# card.net
KiCad netlist of a schematic drawn in EAGLE
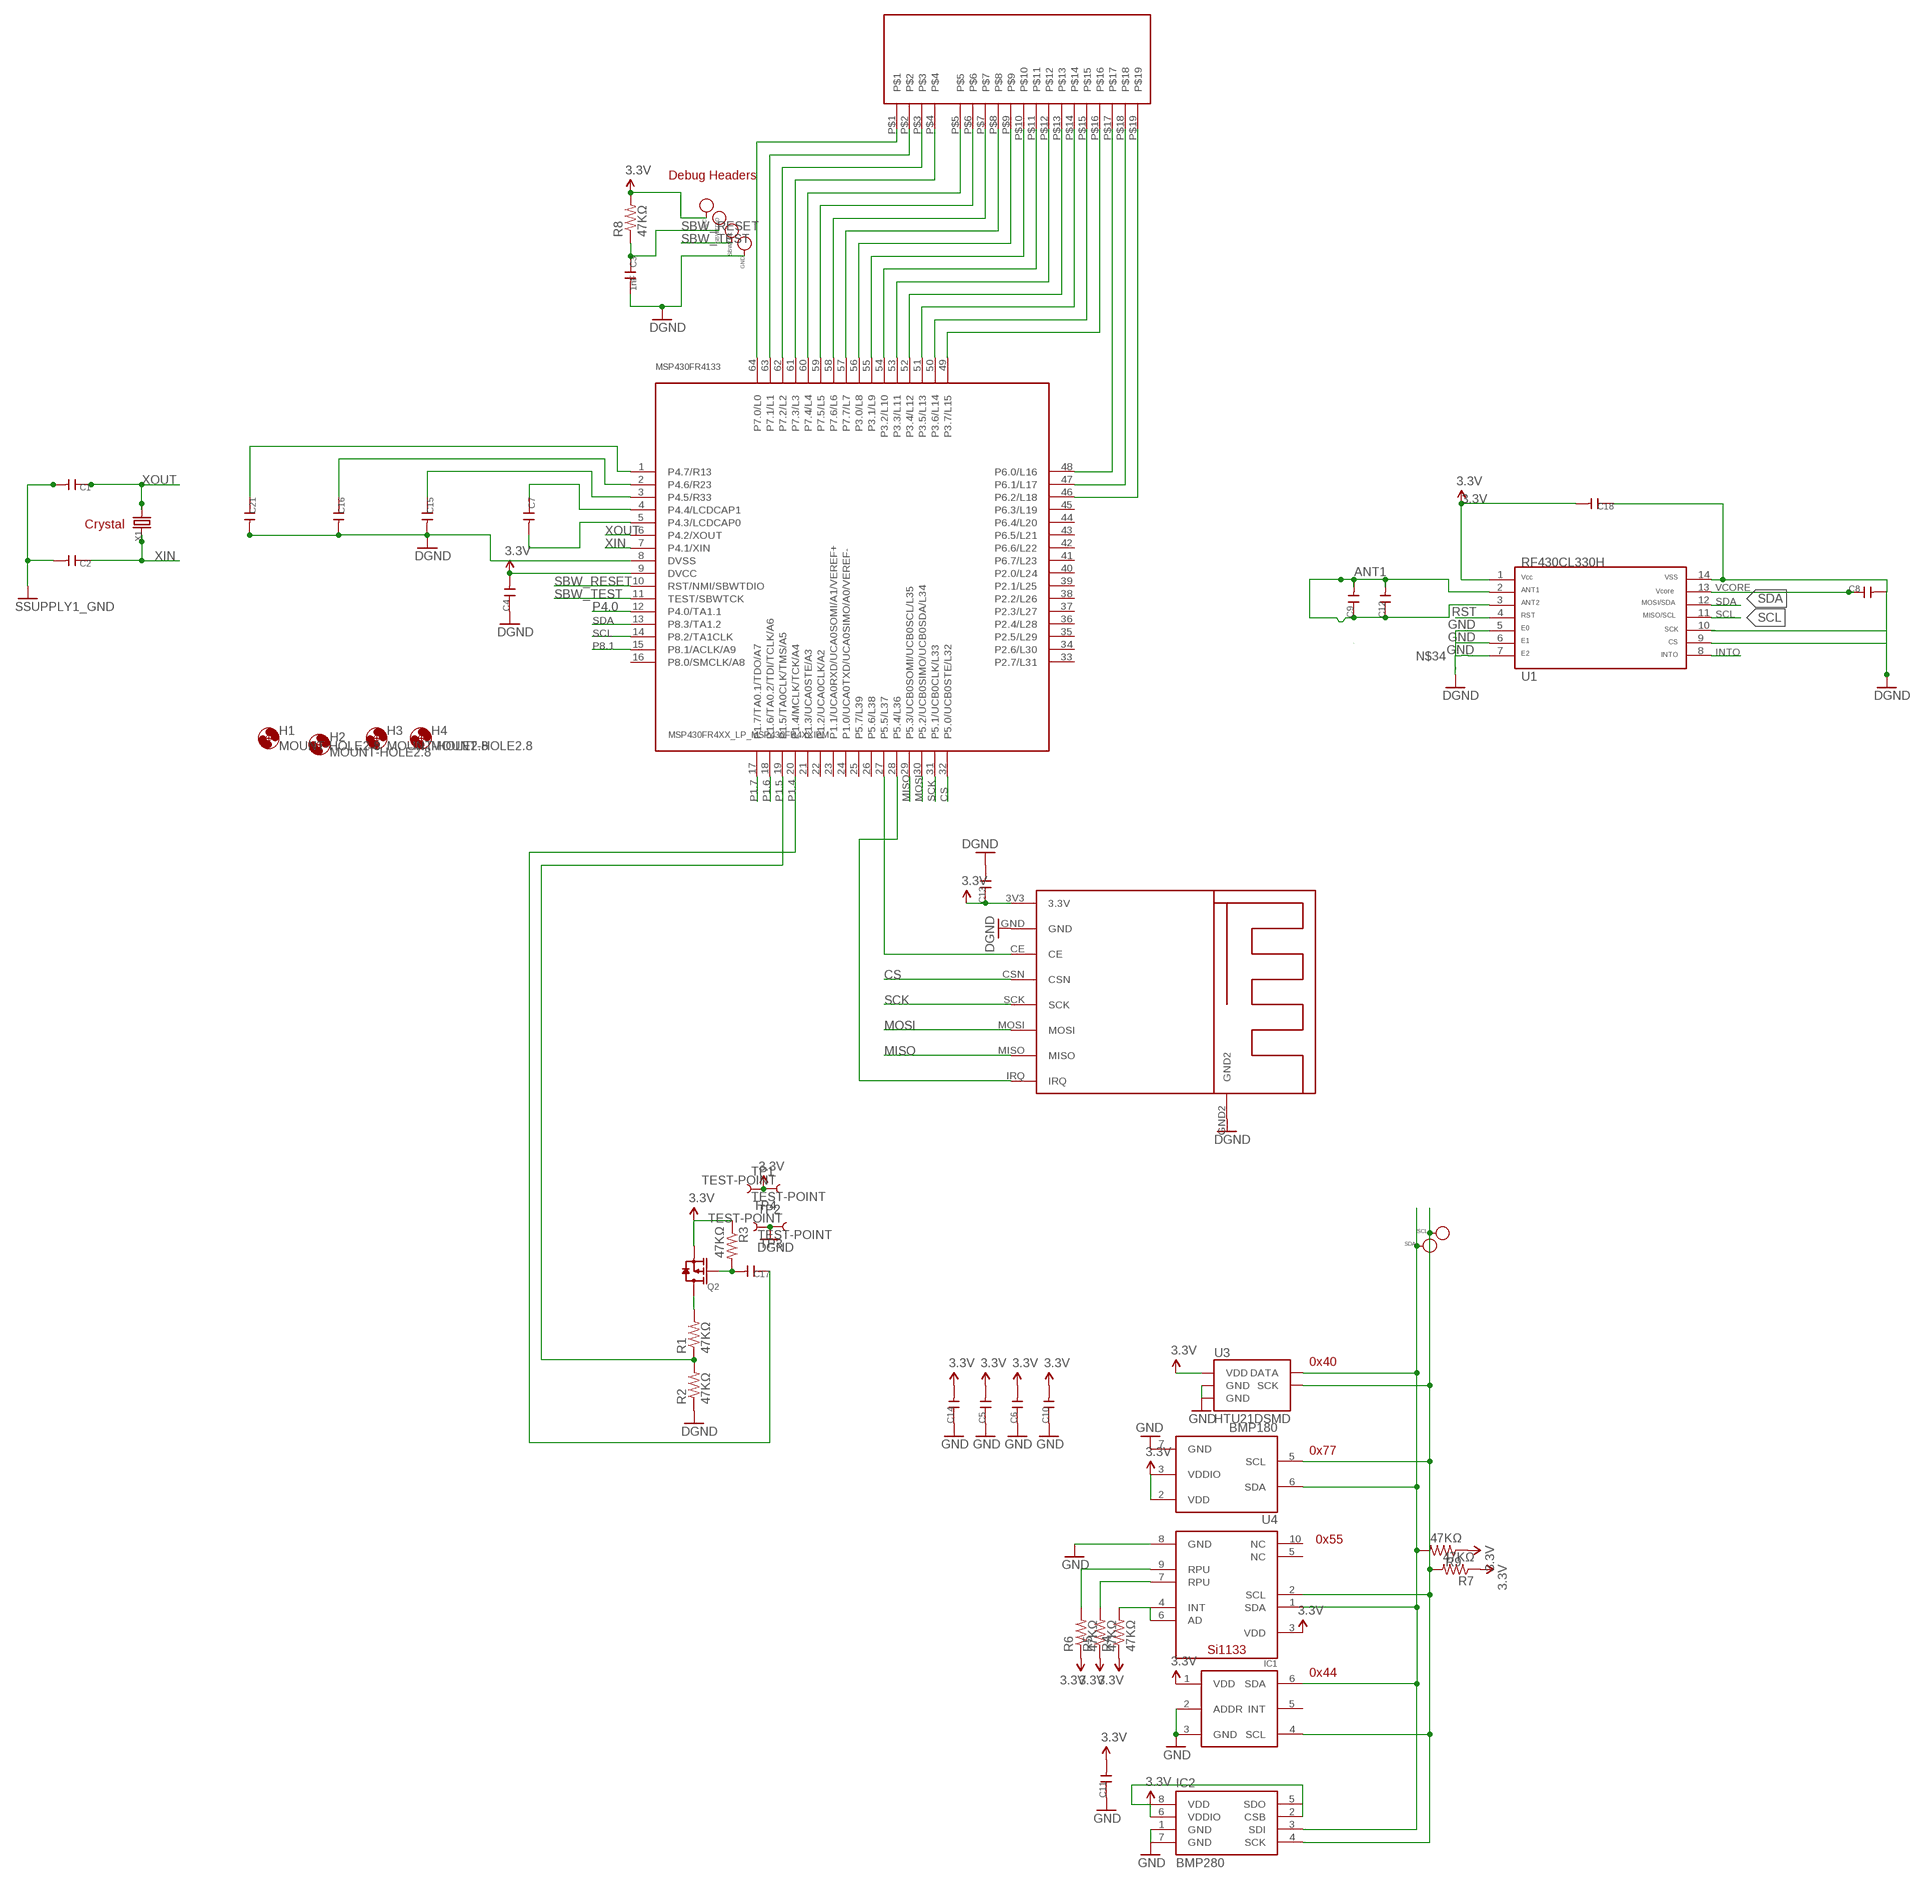
[diagram p0: schematic, sheet 1]

(export (version "E")
  (design (tool "Eeschema 10.0.6"))
  (components
    (comp (ref "C1")
      (value "C-0402")
      (footprint "eagle-import:C0402")
      (libsource (lib "eagle-import") (part "C-0402"))
    )
    (comp (ref "C2")
      (value "C-0402")
      (footprint "eagle-import:C0402")
      (libsource (lib "eagle-import") (part "C-0402"))
    )
    (comp (ref "C3")
      (value "1nF")
      (footprint "eagle-import:C0402")
      (libsource (lib "eagle-import") (part "C-0402"))
    )
    (comp (ref "C4")
      (value "C-0402")
      (footprint "eagle-import:C0402")
      (libsource (lib "eagle-import") (part "C-0402"))
    )
    (comp (ref "C5")
      (value "C-0402")
      (footprint "eagle-import:C0402")
      (libsource (lib "eagle-import") (part "C-0402"))
    )
    (comp (ref "C6")
      (value "C-0402")
      (footprint "eagle-import:C0402")
      (libsource (lib "eagle-import") (part "C-0402"))
    )
    (comp (ref "C7")
      (value "C-0402")
      (footprint "eagle-import:C0402")
      (libsource (lib "eagle-import") (part "C-0402"))
    )
    (comp (ref "C8")
      (value "C-0402")
      (footprint "eagle-import:C0402")
      (libsource (lib "eagle-import") (part "C-0402"))
    )
    (comp (ref "C9")
      (value "C-0402")
      (footprint "eagle-import:C0402")
      (libsource (lib "eagle-import") (part "C-0402"))
    )
    (comp (ref "C10")
      (value "C-0402")
      (footprint "eagle-import:C0402")
      (libsource (lib "eagle-import") (part "C-0402"))
    )
    (comp (ref "C11")
      (value "C-0402")
      (footprint "eagle-import:C0402")
      (libsource (lib "eagle-import") (part "C-0402"))
    )
    (comp (ref "C12")
      (value "C-0402")
      (footprint "eagle-import:C0402")
      (libsource (lib "eagle-import") (part "C-0402"))
    )
    (comp (ref "C13")
      (value "C-0603")
      (footprint "eagle-import:C0603")
      (libsource (lib "eagle-import") (part "C-0603"))
    )
    (comp (ref "C14")
      (value "C-0402")
      (footprint "eagle-import:C0402")
      (libsource (lib "eagle-import") (part "C-0402"))
    )
    (comp (ref "C15")
      (value "C-0402")
      (footprint "eagle-import:C0402")
      (libsource (lib "eagle-import") (part "C-0402"))
    )
    (comp (ref "C16")
      (value "C-0402")
      (footprint "eagle-import:C0402")
      (libsource (lib "eagle-import") (part "C-0402"))
    )
    (comp (ref "C17")
      (value "C-0402")
      (footprint "eagle-import:C0402")
      (libsource (lib "eagle-import") (part "C-0402"))
    )
    (comp (ref "C18")
      (value "C-0402")
      (footprint "eagle-import:C0402")
      (libsource (lib "eagle-import") (part "C-0402"))
    )
    (comp (ref "C21")
      (value "C-0402")
      (footprint "eagle-import:C0402")
      (libsource (lib "eagle-import") (part "C-0402"))
    )
    (comp (ref "GND")
      (value "PAD-TEST-POINT'4545'")
      (footprint "eagle-import:TP_4545")
      (fields (field (name "PARTNO") "DNP"))
      (libsource (lib "eagle-import") (part "PAD-TEST-POINT'4545'"))
    )
    (comp (ref "H1")
      (value "MOUNT-HOLE2.8")
      (footprint "eagle-import:2,8")
      (libsource (lib "eagle-import") (part "MOUNT-HOLE2.8"))
    )
    (comp (ref "H2")
      (value "MOUNT-HOLE2.8")
      (footprint "eagle-import:2,8")
      (libsource (lib "eagle-import") (part "MOUNT-HOLE2.8"))
    )
    (comp (ref "H3")
      (value "MOUNT-HOLE2.8")
      (footprint "eagle-import:2,8")
      (libsource (lib "eagle-import") (part "MOUNT-HOLE2.8"))
    )
    (comp (ref "H4")
      (value "MOUNT-HOLE2.8")
      (footprint "eagle-import:2,8")
      (libsource (lib "eagle-import") (part "MOUNT-HOLE2.8"))
    )
    (comp (ref "IC1")
      (value "SILICONLABS-SI1133")
      (footprint "eagle-import:SILICONLABS-SI1133")
      (libsource (lib "eagle-import") (part "SILICONLABS-SI1133"))
    )
    (comp (ref "IC2")
      (value "BMP280")
      (footprint "eagle-import:LGA")
      (libsource (lib "eagle-import") (part "BMP280"))
    )
    (comp (ref "MSP430FR4133")
      (value "MSP430FR4XX_LP_MSP430FR4XXIPM")
      (footprint "eagle-import:MSP430G6_LP_LQFP64")
      (libsource (lib "eagle-import") (part "MSP430FR4XX_LP_MSP430FR4XXIPM"))
    )
    (comp (ref "Q2")
      (value "MOSFET-P'SI2323CDS/SI2305DS<BR>'")
      (footprint "eagle-import:SOT23")
      (libsource (lib "eagle-import") (part "MOSFET-P'SI2323CDS/SI2305DS{lt}BR{gt}'"))
    )
    (comp (ref "R1")
      (value "47KΩ")
      (footprint "eagle-import:RCL_R1005")
      (libsource (lib "eagle-import") (part "RESISTOR_1005"))
    )
    (comp (ref "R2")
      (value "47KΩ")
      (footprint "eagle-import:RCL_R1005")
      (libsource (lib "eagle-import") (part "RESISTOR_1005"))
    )
    (comp (ref "R3")
      (value "47KΩ")
      (footprint "eagle-import:RCL_R1005")
      (libsource (lib "eagle-import") (part "RESISTOR_1005"))
    )
    (comp (ref "R4")
      (value "47KΩ")
      (footprint "eagle-import:RCL_R1005")
      (libsource (lib "eagle-import") (part "RESISTOR_1005"))
    )
    (comp (ref "R5")
      (value "47KΩ")
      (footprint "eagle-import:RCL_R1005")
      (libsource (lib "eagle-import") (part "RESISTOR_1005"))
    )
    (comp (ref "R6")
      (value "47KΩ")
      (footprint "eagle-import:RCL_R1005")
      (libsource (lib "eagle-import") (part "RESISTOR_1005"))
    )
    (comp (ref "R7")
      (value "47KΩ")
      (footprint "eagle-import:RCL_R1005")
      (libsource (lib "eagle-import") (part "RESISTOR_1005"))
    )
    (comp (ref "R8")
      (value "47KΩ")
      (footprint "eagle-import:RCL_R1005")
      (libsource (lib "eagle-import") (part "RESISTOR_1005"))
    )
    (comp (ref "R9")
      (value "47KΩ")
      (footprint "eagle-import:RCL_R1005")
      (libsource (lib "eagle-import") (part "RESISTOR_1005"))
    )
    (comp (ref "SBWTCK")
      (value "PAD-TEST-POINT'4545'")
      (footprint "eagle-import:TP_4545")
      (fields (field (name "PARTNO") "DNP"))
      (libsource (lib "eagle-import") (part "PAD-TEST-POINT'4545'"))
    )
    (comp (ref "SBWTDIO")
      (value "PAD-TEST-POINT'4545'")
      (footprint "eagle-import:TP_4545")
      (fields (field (name "PARTNO") "DNP"))
      (libsource (lib "eagle-import") (part "PAD-TEST-POINT'4545'"))
    )
    (comp (ref "SCL")
      (value "PAD-TEST-POINT'4545'")
      (footprint "eagle-import:TP_4545")
      (fields (field (name "PARTNO") "DNP"))
      (libsource (lib "eagle-import") (part "PAD-TEST-POINT'4545'"))
    )
    (comp (ref "SDA")
      (value "PAD-TEST-POINT'4545'")
      (footprint "eagle-import:TP_4545")
      (fields (field (name "PARTNO") "DNP"))
      (libsource (lib "eagle-import") (part "PAD-TEST-POINT'4545'"))
    )
    (comp (ref "TP1")
      (value "TEST-POINT")
      (footprint "eagle-import:BATTERY")
      (libsource (lib "eagle-import") (part "TEST-POINT"))
    )
    (comp (ref "TP2")
      (value "TEST-POINT")
      (footprint "eagle-import:BATTERY")
      (libsource (lib "eagle-import") (part "TEST-POINT"))
    )
    (comp (ref "TP3")
      (value "TEST-POINT")
      (footprint "eagle-import:BATTERY")
      (libsource (lib "eagle-import") (part "TEST-POINT"))
    )
    (comp (ref "TP4")
      (value "TEST-POINT")
      (footprint "eagle-import:BATTERY")
      (libsource (lib "eagle-import") (part "TEST-POINT"))
    )
    (comp (ref "U$1")
      (value "HUMIDITYTEMP_DISPLAY")
      (footprint "eagle-import:HUMIDITYTEMP_DISPLAY")
      (libsource (lib "eagle-import") (part "HUMIDITYTEMP_DISPLAY"))
    )
    (comp (ref "U$2")
      (value "NRF24MINI")
      (footprint "eagle-import:NRF24MINI")
      (libsource (lib "eagle-import") (part "NRF24MINI"))
    )
    (comp (ref "U$5")
      (value "TI-OPT3001")
      (footprint "eagle-import:TI-OPT3001")
      (libsource (lib "eagle-import") (part "TI-OPT3001"))
    )
    (comp (ref "U1")
      (value "RF430CL330H")
      (footprint "eagle-import:PW14")
      (libsource (lib "eagle-import") (part "RF430CL330H"))
    )
    (comp (ref "U3")
      (value "HTU21DSMD")
      (footprint "eagle-import:HTU21D")
      (libsource (lib "eagle-import") (part "HTU21DSMD"))
    )
    (comp (ref "U4")
      (value "BMP180")
      (footprint "eagle-import:BMP180")
      (libsource (lib "eagle-import") (part "BMP180"))
    )
    (comp (ref "VCC")
      (value "PAD-TEST-POINT'4545'")
      (footprint "eagle-import:TP_4545")
      (fields (field (name "PARTNO") "DNP"))
      (libsource (lib "eagle-import") (part "PAD-TEST-POINT'4545'"))
    )
    (comp (ref "X1")
      (value "CRYSTAL-3215")
      (footprint "eagle-import:2P-SMD-3.2X1.5")
      (libsource (lib "eagle-import") (part "CRYSTAL-3215"))
    )
  )
  (nets
    (net (code "1") (name "/ANT1") (class "Default")
      (node (ref "C12") (pin "1") (pinfunction "1_1") (pintype "passive"))
      (node (ref "C12") (pin "2") (pinfunction "2_2") (pintype "passive"))
      (node (ref "C9") (pin "1") (pinfunction "1_1") (pintype "passive"))
      (node (ref "C9") (pin "2") (pinfunction "2_2") (pintype "passive"))
      (node (ref "U1") (pin "2") (pinfunction "2_2") (pintype "bidirectional"))
      (node (ref "U1") (pin "3") (pinfunction "3_3") (pintype "bidirectional"))
    )
    (net (code "2") (name "/CS") (class "Default")
      (node (ref "MSP430FR4133") (pin "32") (pinfunction "P5.0/UCB0STE/L32_32") (pintype "bidirectional"))
      (node (ref "U$2") (pin "CSN") (pinfunction "CSN_CSN") (pintype "bidirectional"))
    )
    (net (code "3") (name "/INTO") (class "Default")
      (node (ref "U1") (pin "8") (pinfunction "8_8") (pintype "bidirectional"))
    )
    (net (code "4") (name "/MISO") (class "Default")
      (node (ref "MSP430FR4133") (pin "29") (pinfunction "P5.3/UCB0SOMI/UCB0SCL/L35_29") (pintype "bidirectional"))
      (node (ref "U$2") (pin "MISO") (pinfunction "MISO_MISO") (pintype "bidirectional"))
    )
    (net (code "5") (name "/MOSI") (class "Default")
      (node (ref "MSP430FR4133") (pin "30") (pinfunction "P5.2/UCB0SIMO/UCB0SDA/L34_30") (pintype "bidirectional"))
      (node (ref "U$2") (pin "MOSI") (pinfunction "MOSI_MOSI") (pintype "bidirectional"))
    )
    (net (code "6") (name "/P1.4") (class "Default")
      (node (ref "MSP430FR4133") (pin "19") (pinfunction "P1.5/TA0CLK/TMS/A5_19") (pintype "bidirectional"))
      (node (ref "R1") (pin "1") (pinfunction "1_1") (pintype "passive"))
      (node (ref "R2") (pin "2") (pinfunction "2_2") (pintype "passive"))
    )
    (net (code "7") (name "/P1.5") (class "Default")
      (node (ref "C17") (pin "1") (pinfunction "1_1") (pintype "passive"))
      (node (ref "MSP430FR4133") (pin "20") (pinfunction "P1.4/MCLK/TCK/A4_20") (pintype "bidirectional"))
    )
    (net (code "8") (name "/P1.6") (class "Default")
      (node (ref "MSP430FR4133") (pin "18") (pinfunction "P1.6/TA0.2/TDI/TCLK/A6_18") (pintype "bidirectional"))
    )
    (net (code "9") (name "/P1.7") (class "Default")
      (node (ref "MSP430FR4133") (pin "17") (pinfunction "P1.7/TA0.1/TDO/A7_17") (pintype "bidirectional"))
    )
    (net (code "10") (name "/P4.0") (class "Default")
      (node (ref "MSP430FR4133") (pin "12") (pinfunction "P4.0/TA1.1_12") (pintype "bidirectional"))
    )
    (net (code "11") (name "/P8.1") (class "Default")
      (node (ref "MSP430FR4133") (pin "15") (pinfunction "P8.1/ACLK/A9_15") (pintype "bidirectional"))
    )
    (net (code "12") (name "/RST") (class "Default")
      (node (ref "U1") (pin "4") (pinfunction "4_4") (pintype "bidirectional"))
    )
    (net (code "13") (name "/SBW_RESET") (class "Default")
      (node (ref "C3") (pin "1") (pinfunction "1_1") (pintype "passive"))
      (node (ref "MSP430FR4133") (pin "10") (pinfunction "RST/NMI/SBWTDIO_10") (pintype "bidirectional"))
      (node (ref "R8") (pin "1") (pinfunction "1_1") (pintype "passive"))
      (node (ref "SBWTDIO") (pin "T") (pinfunction "T_T") (pintype "bidirectional"))
    )
    (net (code "14") (name "/SBW_TEST") (class "Default")
      (node (ref "MSP430FR4133") (pin "11") (pinfunction "TEST/SBWTCK_11") (pintype "bidirectional"))
      (node (ref "SBWTCK") (pin "T") (pinfunction "T_T") (pintype "bidirectional"))
    )
    (net (code "15") (name "/SCK") (class "Default")
      (node (ref "MSP430FR4133") (pin "31") (pinfunction "P5.1/UCB0CLK/L33_31") (pintype "bidirectional"))
      (node (ref "U$2") (pin "SCK") (pinfunction "SCK_SCK") (pintype "bidirectional"))
    )
    (net (code "16") (name "/VCORE") (class "Default")
      (node (ref "C8") (pin "1") (pinfunction "1_1") (pintype "passive"))
      (node (ref "U1") (pin "13") (pinfunction "13_13") (pintype "bidirectional"))
    )
    (net (code "17") (name "/XIN") (class "Default")
      (node (ref "C2") (pin "1") (pinfunction "1_1") (pintype "passive"))
      (node (ref "MSP430FR4133") (pin "7") (pinfunction "P4.1/XIN_7") (pintype "bidirectional"))
      (node (ref "X1") (pin "1") (pinfunction "1_1") (pintype "passive"))
    )
    (net (code "18") (name "/XOUT") (class "Default")
      (node (ref "C1") (pin "1") (pinfunction "1_1") (pintype "passive"))
      (node (ref "MSP430FR4133") (pin "6") (pinfunction "P4.2/XOUT_6") (pintype "bidirectional"))
      (node (ref "X1") (pin "2") (pinfunction "2_2") (pintype "passive"))
    )
    (net (code "19") (name "3.3V") (class "Default")
      (node (ref "C10") (pin "2") (pinfunction "2_2") (pintype "passive"))
      (node (ref "C11") (pin "2") (pinfunction "2_2") (pintype "passive"))
      (node (ref "C13") (pin "1") (pinfunction "1_1") (pintype "passive"))
      (node (ref "C14") (pin "2") (pinfunction "2_2") (pintype "passive"))
      (node (ref "C18") (pin "2") (pinfunction "2_2") (pintype "passive"))
      (node (ref "C4") (pin "2") (pinfunction "2_2") (pintype "passive"))
      (node (ref "C5") (pin "2") (pinfunction "2_2") (pintype "passive"))
      (node (ref "C6") (pin "2") (pinfunction "2_2") (pintype "passive"))
      (node (ref "IC1") (pin "3") (pinfunction "VDD_3") (pintype "bidirectional"))
      (node (ref "IC2") (pin "2") (pinfunction "CSB_2") (pintype "input"))
      (node (ref "IC2") (pin "5") (pinfunction "SDO_5") (pintype "bidirectional"))
      (node (ref "IC2") (pin "6") (pinfunction "VDDIO_6") (pintype "input"))
      (node (ref "IC2") (pin "8") (pinfunction "VDD_8") (pintype "power_in"))
      (node (ref "MSP430FR4133") (pin "9") (pinfunction "DVCC_9") (pintype "bidirectional"))
      (node (ref "Q2") (pin "2") (pinfunction "S_2") (pintype "passive"))
      (node (ref "R3") (pin "1") (pinfunction "1_1") (pintype "passive"))
      (node (ref "R4") (pin "1") (pinfunction "1_1") (pintype "passive"))
      (node (ref "R5") (pin "1") (pinfunction "1_1") (pintype "passive"))
      (node (ref "R6") (pin "1") (pinfunction "1_1") (pintype "passive"))
      (node (ref "R7") (pin "1") (pinfunction "1_1") (pintype "passive"))
      (node (ref "R8") (pin "2") (pinfunction "2_2") (pintype "passive"))
      (node (ref "R9") (pin "1") (pinfunction "1_1") (pintype "passive"))
      (node (ref "TP1") (pin "P$1") (pinfunction "1_P$1") (pintype "bidirectional"))
      (node (ref "TP4") (pin "P$1") (pinfunction "1_P$1") (pintype "bidirectional"))
      (node (ref "U$2") (pin "3V3") (pinfunction "3.3V_3V3") (pintype "bidirectional"))
      (node (ref "U$5") (pin "1") (pinfunction "VDD_1") (pintype "bidirectional"))
      (node (ref "U1") (pin "1") (pinfunction "1_1") (pintype "bidirectional"))
      (node (ref "U3") (pin "VDD") (pinfunction "VDD_VDD") (pintype "power_in"))
      (node (ref "U4") (pin "2") (pinfunction "VDD_2") (pintype "power_in"))
      (node (ref "U4") (pin "3") (pinfunction "VDDIO_3") (pintype "power_in"))
      (node (ref "VCC") (pin "T") (pinfunction "T_T") (pintype "bidirectional"))
    )
    (net (code "20") (name "DGND") (class "Default")
      (node (ref "C1") (pin "2") (pinfunction "2_2") (pintype "passive"))
      (node (ref "C10") (pin "1") (pinfunction "1_1") (pintype "passive"))
      (node (ref "C11") (pin "1") (pinfunction "1_1") (pintype "passive"))
      (node (ref "C13") (pin "2") (pinfunction "2_2") (pintype "passive"))
      (node (ref "C14") (pin "1") (pinfunction "1_1") (pintype "passive"))
      (node (ref "C15") (pin "2") (pinfunction "2_2") (pintype "passive"))
      (node (ref "C16") (pin "2") (pinfunction "2_2") (pintype "passive"))
      (node (ref "C18") (pin "1") (pinfunction "1_1") (pintype "passive"))
      (node (ref "C2") (pin "2") (pinfunction "2_2") (pintype "passive"))
      (node (ref "C21") (pin "2") (pinfunction "2_2") (pintype "passive"))
      (node (ref "C3") (pin "2") (pinfunction "2_2") (pintype "passive"))
      (node (ref "C4") (pin "1") (pinfunction "1_1") (pintype "passive"))
      (node (ref "C5") (pin "1") (pinfunction "1_1") (pintype "passive"))
      (node (ref "C6") (pin "1") (pinfunction "1_1") (pintype "passive"))
      (node (ref "C8") (pin "2") (pinfunction "2_2") (pintype "passive"))
      (node (ref "GND") (pin "T") (pinfunction "T_T") (pintype "bidirectional"))
      (node (ref "IC1") (pin "8") (pinfunction "GND_8") (pintype "bidirectional"))
      (node (ref "IC2") (pin "1") (pinfunction "GND_1") (pintype "power_in"))
      (node (ref "IC2") (pin "7") (pinfunction "GND_7") (pintype "power_in"))
      (node (ref "MSP430FR4133") (pin "8") (pinfunction "DVSS_8") (pintype "bidirectional"))
      (node (ref "R2") (pin "1") (pinfunction "1_1") (pintype "passive"))
      (node (ref "TP2") (pin "P$1") (pinfunction "1_P$1") (pintype "bidirectional"))
      (node (ref "TP3") (pin "P$1") (pinfunction "1_P$1") (pintype "bidirectional"))
      (node (ref "U$2") (pin "GND") (pinfunction "GND_GND") (pintype "bidirectional"))
      (node (ref "U$2") (pin "GND2") (pinfunction "GND2_GND2") (pintype "bidirectional"))
      (node (ref "U$5") (pin "2") (pinfunction "ADDR_2") (pintype "bidirectional"))
      (node (ref "U$5") (pin "3") (pinfunction "GND_3") (pintype "bidirectional"))
      (node (ref "U1") (pin "10") (pinfunction "10_10") (pintype "bidirectional"))
      (node (ref "U1") (pin "14") (pinfunction "14_14") (pintype "bidirectional"))
      (node (ref "U1") (pin "5") (pinfunction "5_5") (pintype "bidirectional"))
      (node (ref "U1") (pin "6") (pinfunction "6_6") (pintype "bidirectional"))
      (node (ref "U1") (pin "7") (pinfunction "7_7") (pintype "bidirectional"))
      (node (ref "U1") (pin "9") (pinfunction "9_9") (pintype "bidirectional"))
      (node (ref "U3") (pin "7") (pinfunction "GND_7") (pintype "power_in"))
      (node (ref "U3") (pin "GND") (pinfunction "GND_GND") (pintype "power_in"))
      (node (ref "U4") (pin "7") (pinfunction "GND_7") (pintype "power_in"))
    )
    (net (code "21") (name "Net-(IC1-AD)") (class "Default")
      (node (ref "IC1") (pin "4") (pinfunction "INT_4") (pintype "bidirectional"))
      (node (ref "IC1") (pin "6") (pinfunction "AD_6") (pintype "bidirectional"))
      (node (ref "R4") (pin "2") (pinfunction "2_2") (pintype "passive"))
    )
    (net (code "22") (name "Net-(IC1-RPU-Pad7)") (class "Default")
      (node (ref "IC1") (pin "7") (pinfunction "RPU_7") (pintype "bidirectional"))
      (node (ref "R5") (pin "2") (pinfunction "2_2") (pintype "passive"))
    )
    (net (code "23") (name "Net-(IC1-RPU-Pad9)") (class "Default")
      (node (ref "IC1") (pin "9") (pinfunction "RPU_9") (pintype "bidirectional"))
      (node (ref "R6") (pin "2") (pinfunction "2_2") (pintype "passive"))
    )
    (net (code "24") (name "Net-(MSP430FR4133-P3.0{slash}L8)") (class "Default")
      (node (ref "MSP430FR4133") (pin "56") (pinfunction "P3.0/L8_56") (pintype "bidirectional"))
      (node (ref "U$1") (pin "P$9") (pinfunction "P$9_P$9") (pintype "bidirectional"))
    )
    (net (code "25") (name "Net-(MSP430FR4133-P3.1{slash}L9)") (class "Default")
      (node (ref "MSP430FR4133") (pin "55") (pinfunction "P3.1/L9_55") (pintype "bidirectional"))
      (node (ref "U$1") (pin "P$10") (pinfunction "P$10_P$10") (pintype "bidirectional"))
    )
    (net (code "26") (name "Net-(MSP430FR4133-P3.2{slash}L10)") (class "Default")
      (node (ref "MSP430FR4133") (pin "54") (pinfunction "P3.2/L10_54") (pintype "bidirectional"))
      (node (ref "U$1") (pin "P$11") (pinfunction "P$11_P$11") (pintype "bidirectional"))
    )
    (net (code "27") (name "Net-(MSP430FR4133-P3.3{slash}L11)") (class "Default")
      (node (ref "MSP430FR4133") (pin "53") (pinfunction "P3.3/L11_53") (pintype "bidirectional"))
      (node (ref "U$1") (pin "P$12") (pinfunction "P$12_P$12") (pintype "bidirectional"))
    )
    (net (code "28") (name "Net-(MSP430FR4133-P3.4{slash}L12)") (class "Default")
      (node (ref "MSP430FR4133") (pin "52") (pinfunction "P3.4/L12_52") (pintype "bidirectional"))
      (node (ref "U$1") (pin "P$13") (pinfunction "P$13_P$13") (pintype "bidirectional"))
    )
    (net (code "29") (name "Net-(MSP430FR4133-P3.5{slash}L13)") (class "Default")
      (node (ref "MSP430FR4133") (pin "51") (pinfunction "P3.5/L13_51") (pintype "bidirectional"))
      (node (ref "U$1") (pin "P$14") (pinfunction "P$14_P$14") (pintype "bidirectional"))
    )
    (net (code "30") (name "Net-(MSP430FR4133-P3.6{slash}L14)") (class "Default")
      (node (ref "MSP430FR4133") (pin "50") (pinfunction "P3.6/L14_50") (pintype "bidirectional"))
      (node (ref "U$1") (pin "P$15") (pinfunction "P$15_P$15") (pintype "bidirectional"))
    )
    (net (code "31") (name "Net-(MSP430FR4133-P3.7{slash}L15)") (class "Default")
      (node (ref "MSP430FR4133") (pin "49") (pinfunction "P3.7/L15_49") (pintype "bidirectional"))
      (node (ref "U$1") (pin "P$16") (pinfunction "P$16_P$16") (pintype "bidirectional"))
    )
    (net (code "32") (name "Net-(MSP430FR4133-P4.3{slash}LCDCAP0)") (class "Default")
      (node (ref "C7") (pin "2") (pinfunction "2_2") (pintype "passive"))
      (node (ref "MSP430FR4133") (pin "5") (pinfunction "P4.3/LCDCAP0_5") (pintype "bidirectional"))
    )
    (net (code "33") (name "Net-(MSP430FR4133-P4.4{slash}LCDCAP1)") (class "Default")
      (node (ref "C7") (pin "1") (pinfunction "1_1") (pintype "passive"))
      (node (ref "MSP430FR4133") (pin "4") (pinfunction "P4.4/LCDCAP1_4") (pintype "bidirectional"))
    )
    (net (code "34") (name "Net-(MSP430FR4133-P4.5{slash}R33)") (class "Default")
      (node (ref "C15") (pin "1") (pinfunction "1_1") (pintype "passive"))
      (node (ref "MSP430FR4133") (pin "3") (pinfunction "P4.5/R33_3") (pintype "bidirectional"))
    )
    (net (code "35") (name "Net-(MSP430FR4133-P4.6{slash}R23)") (class "Default")
      (node (ref "C16") (pin "1") (pinfunction "1_1") (pintype "passive"))
      (node (ref "MSP430FR4133") (pin "2") (pinfunction "P4.6/R23_2") (pintype "bidirectional"))
    )
    (net (code "36") (name "Net-(MSP430FR4133-P4.7{slash}R13)") (class "Default")
      (node (ref "C21") (pin "1") (pinfunction "1_1") (pintype "passive"))
      (node (ref "MSP430FR4133") (pin "1") (pinfunction "P4.7/R13_1") (pintype "bidirectional"))
    )
    (net (code "37") (name "Net-(MSP430FR4133-P5.4{slash}L36)") (class "Default")
      (node (ref "MSP430FR4133") (pin "28") (pinfunction "P5.4/L36_28") (pintype "bidirectional"))
      (node (ref "U$2") (pin "IRQ") (pinfunction "IRQ_IRQ") (pintype "bidirectional"))
    )
    (net (code "38") (name "Net-(MSP430FR4133-P5.5{slash}L37)") (class "Default")
      (node (ref "MSP430FR4133") (pin "27") (pinfunction "P5.5/L37_27") (pintype "bidirectional"))
      (node (ref "U$2") (pin "CE") (pinfunction "CE_CE") (pintype "bidirectional"))
    )
    (net (code "39") (name "Net-(MSP430FR4133-P6.0{slash}L16)") (class "Default")
      (node (ref "MSP430FR4133") (pin "48") (pinfunction "P6.0/L16_48") (pintype "bidirectional"))
      (node (ref "U$1") (pin "P$17") (pinfunction "P$17_P$17") (pintype "bidirectional"))
    )
    (net (code "40") (name "Net-(MSP430FR4133-P6.1{slash}L17)") (class "Default")
      (node (ref "MSP430FR4133") (pin "47") (pinfunction "P6.1/L17_47") (pintype "bidirectional"))
      (node (ref "U$1") (pin "P$18") (pinfunction "P$18_P$18") (pintype "bidirectional"))
    )
    (net (code "41") (name "Net-(MSP430FR4133-P6.2{slash}L18)") (class "Default")
      (node (ref "MSP430FR4133") (pin "46") (pinfunction "P6.2/L18_46") (pintype "bidirectional"))
      (node (ref "U$1") (pin "P$19") (pinfunction "P$19_P$19") (pintype "bidirectional"))
    )
    (net (code "42") (name "Net-(MSP430FR4133-P7.0{slash}L0)") (class "Default")
      (node (ref "MSP430FR4133") (pin "64") (pinfunction "P7.0/L0_64") (pintype "bidirectional"))
      (node (ref "U$1") (pin "P$1") (pinfunction "P$1_P$1") (pintype "bidirectional"))
    )
    (net (code "43") (name "Net-(MSP430FR4133-P7.1{slash}L1)") (class "Default")
      (node (ref "MSP430FR4133") (pin "63") (pinfunction "P7.1/L1_63") (pintype "bidirectional"))
      (node (ref "U$1") (pin "P$2") (pinfunction "P$2_P$2") (pintype "bidirectional"))
    )
    (net (code "44") (name "Net-(MSP430FR4133-P7.2{slash}L2)") (class "Default")
      (node (ref "MSP430FR4133") (pin "62") (pinfunction "P7.2/L2_62") (pintype "bidirectional"))
      (node (ref "U$1") (pin "P$3") (pinfunction "P$3_P$3") (pintype "bidirectional"))
    )
    (net (code "45") (name "Net-(MSP430FR4133-P7.3{slash}L3)") (class "Default")
      (node (ref "MSP430FR4133") (pin "61") (pinfunction "P7.3/L3_61") (pintype "bidirectional"))
      (node (ref "U$1") (pin "P$4") (pinfunction "P$4_P$4") (pintype "bidirectional"))
    )
    (net (code "46") (name "Net-(MSP430FR4133-P7.4{slash}L4)") (class "Default")
      (node (ref "MSP430FR4133") (pin "60") (pinfunction "P7.4/L4_60") (pintype "bidirectional"))
      (node (ref "U$1") (pin "P$5") (pinfunction "P$5_P$5") (pintype "bidirectional"))
    )
    (net (code "47") (name "Net-(MSP430FR4133-P7.5{slash}L5)") (class "Default")
      (node (ref "MSP430FR4133") (pin "59") (pinfunction "P7.5/L5_59") (pintype "bidirectional"))
      (node (ref "U$1") (pin "P$6") (pinfunction "P$6_P$6") (pintype "bidirectional"))
    )
    (net (code "48") (name "Net-(MSP430FR4133-P7.6{slash}L6)") (class "Default")
      (node (ref "MSP430FR4133") (pin "58") (pinfunction "P7.6/L6_58") (pintype "bidirectional"))
      (node (ref "U$1") (pin "P$7") (pinfunction "P$7_P$7") (pintype "bidirectional"))
    )
    (net (code "49") (name "Net-(MSP430FR4133-P7.7{slash}L7)") (class "Default")
      (node (ref "MSP430FR4133") (pin "57") (pinfunction "P7.7/L7_57") (pintype "bidirectional"))
      (node (ref "U$1") (pin "P$8") (pinfunction "P$8_P$8") (pintype "bidirectional"))
    )
    (net (code "50") (name "Net-(Q2-D)") (class "Default")
      (node (ref "Q2") (pin "3") (pinfunction "D_3") (pintype "passive"))
      (node (ref "R1") (pin "2") (pinfunction "2_2") (pintype "passive"))
    )
    (net (code "51") (name "Net-(Q2-G)") (class "Default")
      (node (ref "C17") (pin "2") (pinfunction "2_2") (pintype "passive"))
      (node (ref "Q2") (pin "1") (pinfunction "G_1") (pintype "passive"))
      (node (ref "R3") (pin "2") (pinfunction "2_2") (pintype "passive"))
    )
    (net (code "52") (name "SCL") (class "Default")
      (node (ref "IC1") (pin "2") (pinfunction "SCL_2") (pintype "bidirectional"))
      (node (ref "IC2") (pin "4") (pinfunction "SCK_4") (pintype "input"))
      (node (ref "MSP430FR4133") (pin "14") (pinfunction "P8.2/TA1CLK_14") (pintype "bidirectional"))
      (node (ref "R7") (pin "2") (pinfunction "2_2") (pintype "passive"))
      (node (ref "SCL") (pin "T") (pinfunction "T_T") (pintype "bidirectional"))
      (node (ref "U$5") (pin "4") (pinfunction "SCL_4") (pintype "bidirectional"))
      (node (ref "U1") (pin "11") (pinfunction "11_11") (pintype "bidirectional"))
      (node (ref "U3") (pin "SCK") (pinfunction "SCK_SCK") (pintype "input"))
      (node (ref "U4") (pin "5") (pinfunction "SCL_5") (pintype "input"))
    )
    (net (code "53") (name "SDA") (class "Default")
      (node (ref "IC1") (pin "1") (pinfunction "SDA_1") (pintype "bidirectional"))
      (node (ref "IC2") (pin "3") (pinfunction "SDI_3") (pintype "bidirectional"))
      (node (ref "MSP430FR4133") (pin "13") (pinfunction "P8.3/TA1.2_13") (pintype "bidirectional"))
      (node (ref "R9") (pin "2") (pinfunction "2_2") (pintype "passive"))
      (node (ref "SDA") (pin "T") (pinfunction "T_T") (pintype "bidirectional"))
      (node (ref "U$5") (pin "6") (pinfunction "SDA_6") (pintype "bidirectional"))
      (node (ref "U1") (pin "12") (pinfunction "12_12") (pintype "bidirectional"))
      (node (ref "U3") (pin "DATA") (pinfunction "DATA_DATA") (pintype "bidirectional"))
      (node (ref "U4") (pin "6") (pinfunction "SDA_6") (pintype "bidirectional"))
    )
    (net (code "54") (name "unconnected-(IC1-NC-Pad5)") (class "Default")
      (node (ref "IC1") (pin "5") (pinfunction "NC_5") (pintype "bidirectional"))
    )
    (net (code "55") (name "unconnected-(IC1-NC-Pad10)") (class "Default")
      (node (ref "IC1") (pin "10") (pinfunction "NC_10") (pintype "bidirectional"))
    )
    (net (code "56") (name "unconnected-(MSP430FR4133-P1.0{slash}UCA0TXD{slash}UCA0SIMO{slash}A0{slash}VEREF--Pad24)") (class "Default")
      (node (ref "MSP430FR4133") (pin "24") (pinfunction "P1.0/UCA0TXD/UCA0SIMO/A0/VEREF-_24") (pintype "bidirectional"))
    )
    (net (code "57") (name "unconnected-(MSP430FR4133-P1.1{slash}UCA0RXD{slash}UCA0SOMI{slash}A1{slash}VEREF+-Pad23)") (class "Default")
      (node (ref "MSP430FR4133") (pin "23") (pinfunction "P1.1/UCA0RXD/UCA0SOMI/A1/VEREF+_23") (pintype "bidirectional"))
    )
    (net (code "58") (name "unconnected-(MSP430FR4133-P1.2{slash}UCA0CLK{slash}A2-Pad22)") (class "Default")
      (node (ref "MSP430FR4133") (pin "22") (pinfunction "P1.2/UCA0CLK/A2_22") (pintype "bidirectional"))
    )
    (net (code "59") (name "unconnected-(MSP430FR4133-P1.3{slash}UCA0STE{slash}A3-Pad21)") (class "Default")
      (node (ref "MSP430FR4133") (pin "21") (pinfunction "P1.3/UCA0STE/A3_21") (pintype "bidirectional"))
    )
    (net (code "60") (name "unconnected-(MSP430FR4133-P2.0{slash}L24-Pad40)") (class "Default")
      (node (ref "MSP430FR4133") (pin "40") (pinfunction "P2.0/L24_40") (pintype "bidirectional"))
    )
    (net (code "61") (name "unconnected-(MSP430FR4133-P2.1{slash}L25-Pad39)") (class "Default")
      (node (ref "MSP430FR4133") (pin "39") (pinfunction "P2.1/L25_39") (pintype "bidirectional"))
    )
    (net (code "62") (name "unconnected-(MSP430FR4133-P2.2{slash}L26-Pad38)") (class "Default")
      (node (ref "MSP430FR4133") (pin "38") (pinfunction "P2.2/L26_38") (pintype "bidirectional"))
    )
    (net (code "63") (name "unconnected-(MSP430FR4133-P2.3{slash}L27-Pad37)") (class "Default")
      (node (ref "MSP430FR4133") (pin "37") (pinfunction "P2.3/L27_37") (pintype "bidirectional"))
    )
    (net (code "64") (name "unconnected-(MSP430FR4133-P2.4{slash}L28-Pad36)") (class "Default")
      (node (ref "MSP430FR4133") (pin "36") (pinfunction "P2.4/L28_36") (pintype "bidirectional"))
    )
    (net (code "65") (name "unconnected-(MSP430FR4133-P2.5{slash}L29-Pad35)") (class "Default")
      (node (ref "MSP430FR4133") (pin "35") (pinfunction "P2.5/L29_35") (pintype "bidirectional"))
    )
    (net (code "66") (name "unconnected-(MSP430FR4133-P2.6{slash}L30-Pad34)") (class "Default")
      (node (ref "MSP430FR4133") (pin "34") (pinfunction "P2.6/L30_34") (pintype "bidirectional"))
    )
    (net (code "67") (name "unconnected-(MSP430FR4133-P2.7{slash}L31-Pad33)") (class "Default")
      (node (ref "MSP430FR4133") (pin "33") (pinfunction "P2.7/L31_33") (pintype "bidirectional"))
    )
    (net (code "68") (name "unconnected-(MSP430FR4133-P5.6{slash}L38-Pad26)") (class "Default")
      (node (ref "MSP430FR4133") (pin "26") (pinfunction "P5.6/L38_26") (pintype "bidirectional"))
    )
    (net (code "69") (name "unconnected-(MSP430FR4133-P5.7{slash}L39-Pad25)") (class "Default")
      (node (ref "MSP430FR4133") (pin "25") (pinfunction "P5.7/L39_25") (pintype "bidirectional"))
    )
    (net (code "70") (name "unconnected-(MSP430FR4133-P6.3{slash}L19-Pad45)") (class "Default")
      (node (ref "MSP430FR4133") (pin "45") (pinfunction "P6.3/L19_45") (pintype "bidirectional"))
    )
    (net (code "71") (name "unconnected-(MSP430FR4133-P6.4{slash}L20-Pad44)") (class "Default")
      (node (ref "MSP430FR4133") (pin "44") (pinfunction "P6.4/L20_44") (pintype "bidirectional"))
    )
    (net (code "72") (name "unconnected-(MSP430FR4133-P6.5{slash}L21-Pad43)") (class "Default")
      (node (ref "MSP430FR4133") (pin "43") (pinfunction "P6.5/L21_43") (pintype "bidirectional"))
    )
    (net (code "73") (name "unconnected-(MSP430FR4133-P6.6{slash}L22-Pad42)") (class "Default")
      (node (ref "MSP430FR4133") (pin "42") (pinfunction "P6.6/L22_42") (pintype "bidirectional"))
    )
    (net (code "74") (name "unconnected-(MSP430FR4133-P6.7{slash}L23-Pad41)") (class "Default")
      (node (ref "MSP430FR4133") (pin "41") (pinfunction "P6.7/L23_41") (pintype "bidirectional"))
    )
    (net (code "75") (name "unconnected-(MSP430FR4133-P8.0{slash}SMCLK{slash}A8-Pad16)") (class "Default")
      (node (ref "MSP430FR4133") (pin "16") (pinfunction "P8.0/SMCLK/A8_16") (pintype "bidirectional"))
    )
    (net (code "76") (name "unconnected-(U$5-INT-Pad5)") (class "Default")
      (node (ref "U$5") (pin "5") (pinfunction "INT_5") (pintype "bidirectional"))
    )
  )
)
